# drive_monofasico_ir21844_vers_o_7_xx.net
KiCad netlist of a schematic drawn in EAGLE
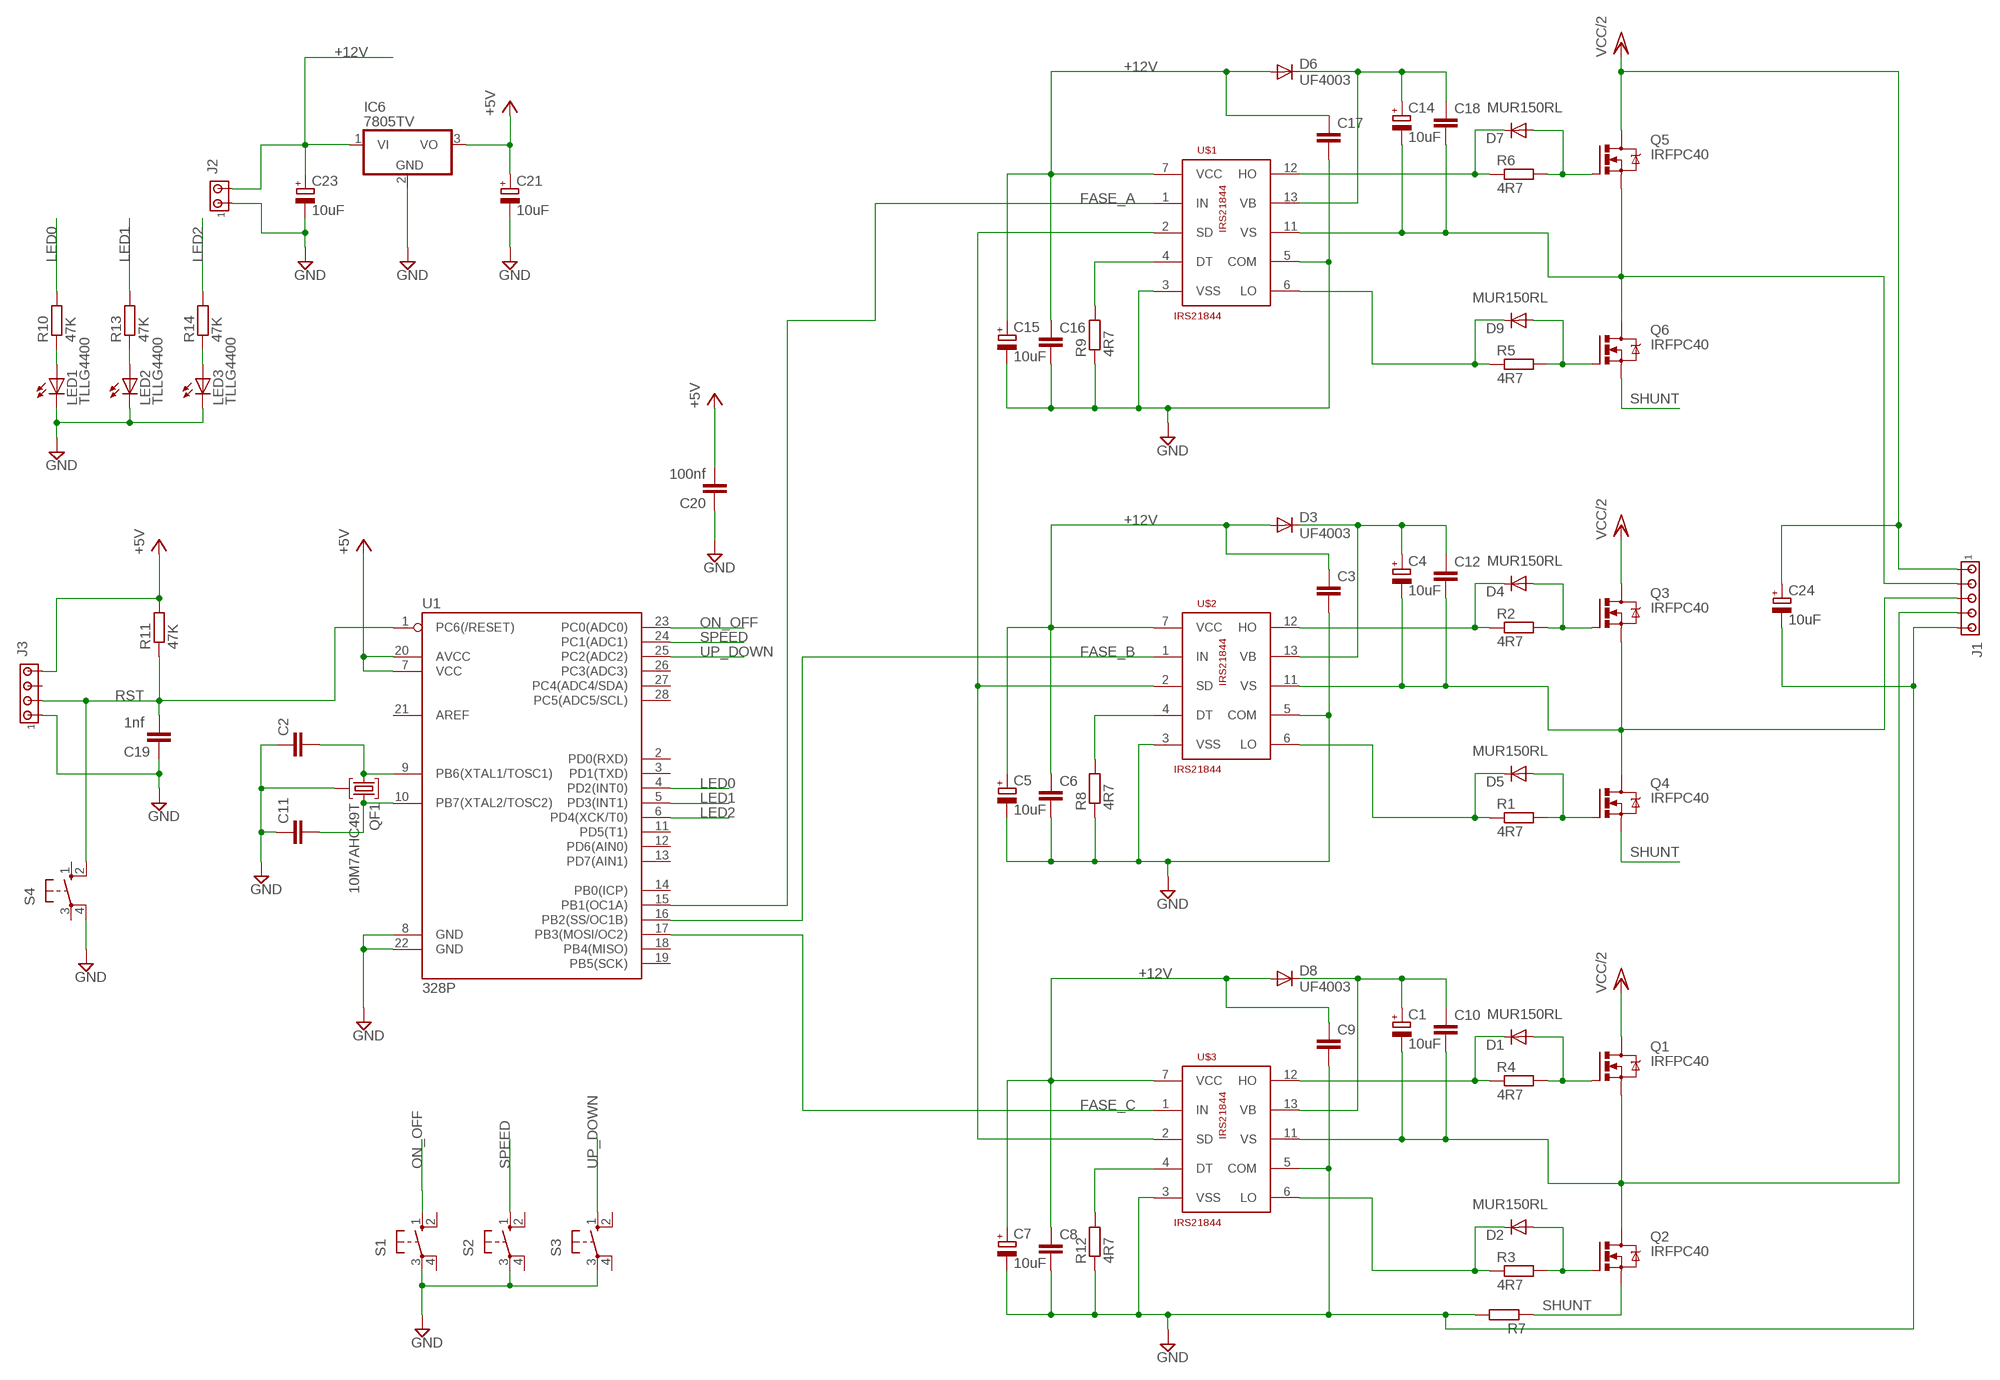
[diagram p0: schematic, sheet 1]

(export (version "E")
  (design (tool "Eeschema 10.0.6"))
  (components
    (comp (ref "C1")
      (value "10uF")
      (footprint "eagle-import:E5-6")
      (libsource (lib "eagle-import") (part "CPOL-EUE5-6"))
    )
    (comp (ref "C2")
      (value "C7.5/3")
      (footprint "eagle-import:C7.5B3")
      (libsource (lib "eagle-import") (part "C7.5/3"))
    )
    (comp (ref "C3")
      (value "C7.5/3")
      (footprint "eagle-import:C7.5B3")
      (libsource (lib "eagle-import") (part "C7.5/3"))
    )
    (comp (ref "C4")
      (value "10uF")
      (footprint "eagle-import:E5-6")
      (libsource (lib "eagle-import") (part "CPOL-EUE5-6"))
    )
    (comp (ref "C5")
      (value "10uF")
      (footprint "eagle-import:E5-6")
      (libsource (lib "eagle-import") (part "CPOL-EUE5-6"))
    )
    (comp (ref "C6")
      (value "C7.5/3")
      (footprint "eagle-import:C7.5B3")
      (libsource (lib "eagle-import") (part "C7.5/3"))
    )
    (comp (ref "C7")
      (value "10uF")
      (footprint "eagle-import:E5-6")
      (libsource (lib "eagle-import") (part "CPOL-EUE5-6"))
    )
    (comp (ref "C8")
      (value "C7.5/3")
      (footprint "eagle-import:C7.5B3")
      (libsource (lib "eagle-import") (part "C7.5/3"))
    )
    (comp (ref "C9")
      (value "C7.5/3")
      (footprint "eagle-import:C7.5B3")
      (libsource (lib "eagle-import") (part "C7.5/3"))
    )
    (comp (ref "C10")
      (value "C7.5/3")
      (footprint "eagle-import:C7.5B3")
      (libsource (lib "eagle-import") (part "C7.5/3"))
    )
    (comp (ref "C11")
      (value "C7.5/3")
      (footprint "eagle-import:C7.5B3")
      (libsource (lib "eagle-import") (part "C7.5/3"))
    )
    (comp (ref "C12")
      (value "C7.5/3")
      (footprint "eagle-import:C7.5B3")
      (libsource (lib "eagle-import") (part "C7.5/3"))
    )
    (comp (ref "C14")
      (value "10uF")
      (footprint "eagle-import:E5-6")
      (libsource (lib "eagle-import") (part "CPOL-EUE5-6"))
    )
    (comp (ref "C15")
      (value "10uF")
      (footprint "eagle-import:E5-6")
      (libsource (lib "eagle-import") (part "CPOL-EUE5-6"))
    )
    (comp (ref "C16")
      (value "C7.5/3")
      (footprint "eagle-import:C7.5B3")
      (libsource (lib "eagle-import") (part "C7.5/3"))
    )
    (comp (ref "C17")
      (value "C7.5/3")
      (footprint "eagle-import:C7.5B3")
      (libsource (lib "eagle-import") (part "C7.5/3"))
    )
    (comp (ref "C18")
      (value "C7.5/3")
      (footprint "eagle-import:C7.5B3")
      (libsource (lib "eagle-import") (part "C7.5/3"))
    )
    (comp (ref "C19")
      (value "1nf")
      (footprint "eagle-import:C050-025X075")
      (libsource (lib "eagle-import") (part "C-EU050-025X075"))
    )
    (comp (ref "C20")
      (value "100nf")
      (footprint "eagle-import:C050-025X075")
      (libsource (lib "eagle-import") (part "C-EU050-025X075"))
    )
    (comp (ref "C21")
      (value "10uF")
      (footprint "eagle-import:E5-6")
      (libsource (lib "eagle-import") (part "CPOL-EUE5-6"))
    )
    (comp (ref "C23")
      (value "10uF")
      (footprint "eagle-import:E5-6")
      (libsource (lib "eagle-import") (part "CPOL-EUE5-6"))
    )
    (comp (ref "C24")
      (value "10uF")
      (footprint "eagle-import:E5-6")
      (libsource (lib "eagle-import") (part "CPOL-EUE5-6"))
    )
    (comp (ref "D1")
      (value "MUR150RL")
      (footprint "eagle-import:DO41-10")
      (libsource (lib "eagle-import") (part "MUR150RL"))
    )
    (comp (ref "D2")
      (value "MUR150RL")
      (footprint "eagle-import:DO41-10")
      (libsource (lib "eagle-import") (part "MUR150RL"))
    )
    (comp (ref "D3")
      (value "UF4003")
      (footprint "eagle-import:DO41-10")
      (libsource (lib "eagle-import") (part "UF4003"))
    )
    (comp (ref "D4")
      (value "MUR150RL")
      (footprint "eagle-import:DO41-10")
      (libsource (lib "eagle-import") (part "MUR150RL"))
    )
    (comp (ref "D5")
      (value "MUR150RL")
      (footprint "eagle-import:DO41-10")
      (libsource (lib "eagle-import") (part "MUR150RL"))
    )
    (comp (ref "D6")
      (value "UF4003")
      (footprint "eagle-import:DO41-10")
      (libsource (lib "eagle-import") (part "UF4003"))
    )
    (comp (ref "D7")
      (value "MUR150RL")
      (footprint "eagle-import:DO41-10")
      (libsource (lib "eagle-import") (part "MUR150RL"))
    )
    (comp (ref "D8")
      (value "UF4003")
      (footprint "eagle-import:DO41-10")
      (libsource (lib "eagle-import") (part "UF4003"))
    )
    (comp (ref "D9")
      (value "MUR150RL")
      (footprint "eagle-import:DO41-10")
      (libsource (lib "eagle-import") (part "MUR150RL"))
    )
    (comp (ref "IC6")
      (value "7805TV")
      (footprint "eagle-import:TO220V")
      (libsource (lib "eagle-import") (part "78TV05"))
    )
    (comp (ref "J1")
      (value "MTA05-156")
      (footprint "eagle-import:1X5MTA")
      (libsource (lib "eagle-import") (part "MTA05-156"))
    )
    (comp (ref "J2")
      (value "MTA02-100")
      (footprint "eagle-import:10X02MTA")
      (libsource (lib "eagle-import") (part "MTA02-100"))
    )
    (comp (ref "J3")
      (value "MTA04-100")
      (footprint "eagle-import:10X04MTA")
      (libsource (lib "eagle-import") (part "MTA04-100"))
    )
    (comp (ref "LED1")
      (value "TLLG4400")
      (footprint "eagle-import:LED3MM")
      (fields (field (name "MF") "VISHAY SEMICONDUCTOR"))
      (libsource (lib "eagle-import") (part "TLLG4400"))
    )
    (comp (ref "LED2")
      (value "TLLG4400")
      (footprint "eagle-import:LED3MM")
      (fields (field (name "MF") "VISHAY SEMICONDUCTOR"))
      (libsource (lib "eagle-import") (part "TLLG4400"))
    )
    (comp (ref "LED3")
      (value "TLLG4400")
      (footprint "eagle-import:LED3MM")
      (fields (field (name "MF") "VISHAY SEMICONDUCTOR"))
      (libsource (lib "eagle-import") (part "TLLG4400"))
    )
    (comp (ref "Q1")
      (value "IRFPC40")
      (footprint "eagle-import:TO247BV")
      (libsource (lib "eagle-import") (part "IRFPC40"))
    )
    (comp (ref "Q2")
      (value "IRFPC40")
      (footprint "eagle-import:TO247BV")
      (libsource (lib "eagle-import") (part "IRFPC40"))
    )
    (comp (ref "Q3")
      (value "IRFPC40")
      (footprint "eagle-import:TO247BV")
      (libsource (lib "eagle-import") (part "IRFPC40"))
    )
    (comp (ref "Q4")
      (value "IRFPC40")
      (footprint "eagle-import:TO247BV")
      (libsource (lib "eagle-import") (part "IRFPC40"))
    )
    (comp (ref "Q5")
      (value "IRFPC40")
      (footprint "eagle-import:TO247BV")
      (libsource (lib "eagle-import") (part "IRFPC40"))
    )
    (comp (ref "Q6")
      (value "IRFPC40")
      (footprint "eagle-import:TO247BV")
      (libsource (lib "eagle-import") (part "IRFPC40"))
    )
    (comp (ref "QF1")
      (value "10M7AHC49T")
      (footprint "eagle-import:HC49U")
      (libsource (lib "eagle-import") (part "10MAHC49T7"))
    )
    (comp (ref "R1")
      (value "4R7")
      (footprint "eagle-import:0207_12")
      (libsource (lib "eagle-import") (part "R-EU_0207/12"))
    )
    (comp (ref "R2")
      (value "4R7")
      (footprint "eagle-import:0207_12")
      (libsource (lib "eagle-import") (part "R-EU_0207/12"))
    )
    (comp (ref "R3")
      (value "4R7")
      (footprint "eagle-import:0207_12")
      (libsource (lib "eagle-import") (part "R-EU_0207/12"))
    )
    (comp (ref "R4")
      (value "4R7")
      (footprint "eagle-import:0207_12")
      (libsource (lib "eagle-import") (part "R-EU_0207/12"))
    )
    (comp (ref "R5")
      (value "4R7")
      (footprint "eagle-import:0207_12")
      (libsource (lib "eagle-import") (part "R-EU_0207/12"))
    )
    (comp (ref "R6")
      (value "4R7")
      (footprint "eagle-import:0207_12")
      (libsource (lib "eagle-import") (part "R-EU_0207/12"))
    )
    (comp (ref "R7")
      (value "R-EU_0613/15")
      (footprint "eagle-import:P0613_15")
      (libsource (lib "eagle-import") (part "resistor_R-EU_0613/15"))
    )
    (comp (ref "R8")
      (value "4R7")
      (footprint "eagle-import:0207_12")
      (libsource (lib "eagle-import") (part "R-EU_0207/12"))
    )
    (comp (ref "R9")
      (value "4R7")
      (footprint "eagle-import:0207_12")
      (libsource (lib "eagle-import") (part "R-EU_0207/12"))
    )
    (comp (ref "R10")
      (value "47K")
      (footprint "eagle-import:0207_12")
      (libsource (lib "eagle-import") (part "resistor_R-EU_0207/12"))
    )
    (comp (ref "R11")
      (value "47K")
      (footprint "eagle-import:0207_12")
      (libsource (lib "eagle-import") (part "resistor_R-EU_0207/12"))
    )
    (comp (ref "R12")
      (value "4R7")
      (footprint "eagle-import:0207_12")
      (libsource (lib "eagle-import") (part "R-EU_0207/12"))
    )
    (comp (ref "R13")
      (value "47K")
      (footprint "eagle-import:0207_12")
      (libsource (lib "eagle-import") (part "resistor_R-EU_0207/12"))
    )
    (comp (ref "R14")
      (value "47K")
      (footprint "eagle-import:0207_12")
      (libsource (lib "eagle-import") (part "resistor_R-EU_0207/12"))
    )
    (comp (ref "S1")
      (value "10-XX")
      (footprint "eagle-import:B3F-10XX")
      (fields (field (name "MPN") "B3F-1000"))
      (libsource (lib "eagle-import") (part "10-XX"))
    )
    (comp (ref "S2")
      (value "10-XX")
      (footprint "eagle-import:B3F-10XX")
      (fields (field (name "MPN") "B3F-1000"))
      (libsource (lib "eagle-import") (part "10-XX"))
    )
    (comp (ref "S3")
      (value "10-XX")
      (footprint "eagle-import:B3F-10XX")
      (fields (field (name "MPN") "B3F-1000"))
      (libsource (lib "eagle-import") (part "10-XX"))
    )
    (comp (ref "S4")
      (value "10-XX")
      (footprint "eagle-import:B3F-10XX")
      (fields (field (name "MPN") "B3F-1000"))
      (libsource (lib "eagle-import") (part "10-XX"))
    )
    (comp (ref "U$1")
      (value "IRS21844")
      (footprint "eagle-import:IRS21844")
      (libsource (lib "eagle-import") (part "IRS21844"))
    )
    (comp (ref "U$2")
      (value "IRS21844")
      (footprint "eagle-import:IRS21844")
      (libsource (lib "eagle-import") (part "IRS21844"))
    )
    (comp (ref "U$3")
      (value "IRS21844")
      (footprint "eagle-import:IRS21844")
      (libsource (lib "eagle-import") (part "IRS21844"))
    )
    (comp (ref "U1")
      (value "328P")
      (footprint "eagle-import:DIP28")
      (libsource (lib "eagle-import") (part "ATMEGA328P_PDIP"))
    )
  )
  (nets
    (net (code "1") (name "+5V") (class "Default")
      (node (ref "C20") (pin "2") (pinfunction "2_2") (pintype "passive"))
      (node (ref "C21") (pin "+") (pinfunction "+_+") (pintype "passive"))
      (node (ref "IC6") (pin "3") (pinfunction "VO_3") (pintype "passive"))
      (node (ref "J3") (pin "4") (pinfunction "4_4") (pintype "passive"))
      (node (ref "R11") (pin "2") (pinfunction "2_2") (pintype "passive"))
      (node (ref "U1") (pin "20") (pinfunction "AVCC_20") (pintype "bidirectional"))
      (node (ref "U1") (pin "7") (pinfunction "VCC_7") (pintype "bidirectional"))
    )
    (net (code "2") (name "/+12V") (class "Default")
      (node (ref "C15") (pin "+") (pinfunction "+_+") (pintype "passive"))
      (node (ref "C16") (pin "1") (pinfunction "1_1") (pintype "passive"))
      (node (ref "C17") (pin "1") (pinfunction "1_1") (pintype "passive"))
      (node (ref "C23") (pin "+") (pinfunction "+_+") (pintype "passive"))
      (node (ref "C3") (pin "1") (pinfunction "1_1") (pintype "passive"))
      (node (ref "C5") (pin "+") (pinfunction "+_+") (pintype "passive"))
      (node (ref "C6") (pin "1") (pinfunction "1_1") (pintype "passive"))
      (node (ref "C7") (pin "+") (pinfunction "+_+") (pintype "passive"))
      (node (ref "C8") (pin "1") (pinfunction "1_1") (pintype "passive"))
      (node (ref "C9") (pin "1") (pinfunction "1_1") (pintype "passive"))
      (node (ref "D3") (pin "A") (pinfunction "A_A") (pintype "passive"))
      (node (ref "D6") (pin "A") (pinfunction "A_A") (pintype "passive"))
      (node (ref "D8") (pin "A") (pinfunction "A_A") (pintype "passive"))
      (node (ref "IC6") (pin "1") (pinfunction "VI_1") (pintype "input"))
      (node (ref "J2") (pin "2") (pinfunction "2_2") (pintype "passive"))
      (node (ref "U$1") (pin "7") (pinfunction "VCC_7") (pintype "bidirectional"))
      (node (ref "U$2") (pin "7") (pinfunction "VCC_7") (pintype "bidirectional"))
      (node (ref "U$3") (pin "7") (pinfunction "VCC_7") (pintype "bidirectional"))
    )
    (net (code "3") (name "/FASE_A") (class "Default")
      (node (ref "U$1") (pin "1") (pinfunction "IN_1") (pintype "bidirectional"))
      (node (ref "U1") (pin "15") (pinfunction "PB1(OC1A)_15") (pintype "bidirectional"))
    )
    (net (code "4") (name "/FASE_B") (class "Default")
      (node (ref "U$2") (pin "1") (pinfunction "IN_1") (pintype "bidirectional"))
      (node (ref "U1") (pin "16") (pinfunction "PB2(SS/OC1B)_16") (pintype "bidirectional"))
    )
    (net (code "5") (name "/FASE_C") (class "Default")
      (node (ref "U$3") (pin "1") (pinfunction "IN_1") (pintype "bidirectional"))
      (node (ref "U1") (pin "17") (pinfunction "PB3(MOSI/OC2)_17") (pintype "bidirectional"))
    )
    (net (code "6") (name "/LED0") (class "Default")
      (node (ref "R10") (pin "2") (pinfunction "2_2") (pintype "passive"))
      (node (ref "U1") (pin "4") (pinfunction "PD2(INT0)_4") (pintype "bidirectional"))
    )
    (net (code "7") (name "/LED1") (class "Default")
      (node (ref "R13") (pin "2") (pinfunction "2_2") (pintype "passive"))
      (node (ref "U1") (pin "5") (pinfunction "PD3(INT1)_5") (pintype "bidirectional"))
    )
    (net (code "8") (name "/LED2") (class "Default")
      (node (ref "R14") (pin "2") (pinfunction "2_2") (pintype "passive"))
      (node (ref "U1") (pin "6") (pinfunction "PD4(XCK/T0)_6") (pintype "bidirectional"))
    )
    (net (code "9") (name "/ON_OFF") (class "Default")
      (node (ref "S1") (pin "1") (pinfunction "S_1") (pintype "passive"))
      (node (ref "U1") (pin "23") (pinfunction "PC0(ADC0)_23") (pintype "bidirectional"))
    )
    (net (code "10") (name "/RST") (class "Default")
      (node (ref "C19") (pin "1") (pinfunction "1_1") (pintype "passive"))
      (node (ref "J3") (pin "2") (pinfunction "2_2") (pintype "passive"))
      (node (ref "R11") (pin "1") (pinfunction "1_1") (pintype "passive"))
      (node (ref "S4") (pin "2") (pinfunction "S1_2") (pintype "passive"))
      (node (ref "U1") (pin "1") (pinfunction "PC6(/RESET)_1") (pintype "bidirectional"))
    )
    (net (code "11") (name "/SHUNT") (class "Default")
      (node (ref "Q2") (pin "S") (pinfunction "S_S") (pintype "passive"))
      (node (ref "Q4") (pin "S") (pinfunction "S_S") (pintype "passive"))
      (node (ref "Q6") (pin "S") (pinfunction "S_S") (pintype "passive"))
      (node (ref "R7") (pin "1") (pinfunction "1_1") (pintype "passive"))
    )
    (net (code "12") (name "/SPEED") (class "Default")
      (node (ref "S2") (pin "1") (pinfunction "S_1") (pintype "passive"))
      (node (ref "U1") (pin "24") (pinfunction "PC1(ADC1)_24") (pintype "bidirectional"))
    )
    (net (code "13") (name "/UP_DOWN") (class "Default")
      (node (ref "S3") (pin "1") (pinfunction "S_1") (pintype "passive"))
      (node (ref "U1") (pin "25") (pinfunction "PC2(ADC2)_25") (pintype "bidirectional"))
    )
    (net (code "14") (name "GND") (class "Default")
      (node (ref "C11") (pin "1") (pinfunction "1_1") (pintype "passive"))
      (node (ref "C15") (pin "-") (pinfunction "-_-") (pintype "passive"))
      (node (ref "C16") (pin "2") (pinfunction "2_2") (pintype "passive"))
      (node (ref "C17") (pin "2") (pinfunction "2_2") (pintype "passive"))
      (node (ref "C19") (pin "2") (pinfunction "2_2") (pintype "passive"))
      (node (ref "C2") (pin "1") (pinfunction "1_1") (pintype "passive"))
      (node (ref "C20") (pin "1") (pinfunction "1_1") (pintype "passive"))
      (node (ref "C21") (pin "-") (pinfunction "-_-") (pintype "passive"))
      (node (ref "C23") (pin "-") (pinfunction "-_-") (pintype "passive"))
      (node (ref "C24") (pin "-") (pinfunction "-_-") (pintype "passive"))
      (node (ref "C3") (pin "2") (pinfunction "2_2") (pintype "passive"))
      (node (ref "C5") (pin "-") (pinfunction "-_-") (pintype "passive"))
      (node (ref "C6") (pin "2") (pinfunction "2_2") (pintype "passive"))
      (node (ref "C7") (pin "-") (pinfunction "-_-") (pintype "passive"))
      (node (ref "C8") (pin "2") (pinfunction "2_2") (pintype "passive"))
      (node (ref "C9") (pin "2") (pinfunction "2_2") (pintype "passive"))
      (node (ref "IC6") (pin "2") (pinfunction "GND_2") (pintype "passive"))
      (node (ref "J1") (pin "5") (pinfunction "5_5") (pintype "passive"))
      (node (ref "J2") (pin "1") (pinfunction "1_1") (pintype "passive"))
      (node (ref "J3") (pin "1") (pinfunction "1_1") (pintype "passive"))
      (node (ref "LED1") (pin "K") (pinfunction "C_K") (pintype "passive"))
      (node (ref "LED2") (pin "K") (pinfunction "C_K") (pintype "passive"))
      (node (ref "LED3") (pin "K") (pinfunction "C_K") (pintype "passive"))
      (node (ref "QF1") (pin "2") (pinfunction "2_2") (pintype "passive"))
      (node (ref "R12") (pin "1") (pinfunction "1_1") (pintype "passive"))
      (node (ref "R7") (pin "2") (pinfunction "2_2") (pintype "passive"))
      (node (ref "R8") (pin "1") (pinfunction "1_1") (pintype "passive"))
      (node (ref "R9") (pin "1") (pinfunction "1_1") (pintype "passive"))
      (node (ref "S1") (pin "3") (pinfunction "P_3") (pintype "passive"))
      (node (ref "S2") (pin "3") (pinfunction "P_3") (pintype "passive"))
      (node (ref "S3") (pin "3") (pinfunction "P_3") (pintype "passive"))
      (node (ref "S4") (pin "4") (pinfunction "P1_4") (pintype "passive"))
      (node (ref "U$1") (pin "3") (pinfunction "VSS_3") (pintype "bidirectional"))
      (node (ref "U$1") (pin "5") (pinfunction "COM_5") (pintype "bidirectional"))
      (node (ref "U$2") (pin "3") (pinfunction "VSS_3") (pintype "bidirectional"))
      (node (ref "U$2") (pin "5") (pinfunction "COM_5") (pintype "bidirectional"))
      (node (ref "U$3") (pin "3") (pinfunction "VSS_3") (pintype "bidirectional"))
      (node (ref "U$3") (pin "5") (pinfunction "COM_5") (pintype "bidirectional"))
      (node (ref "U1") (pin "22") (pinfunction "GND_22") (pintype "bidirectional"))
      (node (ref "U1") (pin "8") (pinfunction "GND_8") (pintype "bidirectional"))
    )
    (net (code "15") (name "Net-(D1-PadA)") (class "Default")
      (node (ref "D1") (pin "A") (pinfunction "A_A") (pintype "passive"))
      (node (ref "Q1") (pin "G") (pinfunction "G_G") (pintype "passive"))
      (node (ref "R4") (pin "2") (pinfunction "2_2") (pintype "passive"))
    )
    (net (code "16") (name "Net-(D2-PadA)") (class "Default")
      (node (ref "D2") (pin "A") (pinfunction "A_A") (pintype "passive"))
      (node (ref "Q2") (pin "G") (pinfunction "G_G") (pintype "passive"))
      (node (ref "R3") (pin "2") (pinfunction "2_2") (pintype "passive"))
    )
    (net (code "17") (name "Net-(D4-PadA)") (class "Default")
      (node (ref "D4") (pin "A") (pinfunction "A_A") (pintype "passive"))
      (node (ref "Q3") (pin "G") (pinfunction "G_G") (pintype "passive"))
      (node (ref "R2") (pin "2") (pinfunction "2_2") (pintype "passive"))
    )
    (net (code "18") (name "Net-(D5-PadA)") (class "Default")
      (node (ref "D5") (pin "A") (pinfunction "A_A") (pintype "passive"))
      (node (ref "Q4") (pin "G") (pinfunction "G_G") (pintype "passive"))
      (node (ref "R1") (pin "2") (pinfunction "2_2") (pintype "passive"))
    )
    (net (code "19") (name "Net-(D7-PadA)") (class "Default")
      (node (ref "D7") (pin "A") (pinfunction "A_A") (pintype "passive"))
      (node (ref "Q5") (pin "G") (pinfunction "G_G") (pintype "passive"))
      (node (ref "R6") (pin "2") (pinfunction "2_2") (pintype "passive"))
    )
    (net (code "20") (name "Net-(D9-PadA)") (class "Default")
      (node (ref "D9") (pin "A") (pinfunction "A_A") (pintype "passive"))
      (node (ref "Q6") (pin "G") (pinfunction "G_G") (pintype "passive"))
      (node (ref "R5") (pin "2") (pinfunction "2_2") (pintype "passive"))
    )
    (net (code "21") (name "Net-(LED1-PadA)") (class "Default")
      (node (ref "LED1") (pin "A") (pinfunction "A_A") (pintype "passive"))
      (node (ref "R10") (pin "1") (pinfunction "1_1") (pintype "passive"))
    )
    (net (code "22") (name "Net-(LED2-PadA)") (class "Default")
      (node (ref "LED2") (pin "A") (pinfunction "A_A") (pintype "passive"))
      (node (ref "R13") (pin "1") (pinfunction "1_1") (pintype "passive"))
    )
    (net (code "23") (name "Net-(LED3-PadA)") (class "Default")
      (node (ref "LED3") (pin "A") (pinfunction "A_A") (pintype "passive"))
      (node (ref "R14") (pin "1") (pinfunction "1_1") (pintype "passive"))
    )
    (net (code "24") (name "Net-(U$1-DT)") (class "Default")
      (node (ref "R9") (pin "2") (pinfunction "2_2") (pintype "passive"))
      (node (ref "U$1") (pin "4") (pinfunction "DT_4") (pintype "bidirectional"))
    )
    (net (code "25") (name "Net-(U$1-HO)") (class "Default")
      (node (ref "D7") (pin "C") (pinfunction "C_C") (pintype "passive"))
      (node (ref "R6") (pin "1") (pinfunction "1_1") (pintype "passive"))
      (node (ref "U$1") (pin "12") (pinfunction "HO_12") (pintype "bidirectional"))
    )
    (net (code "26") (name "Net-(U$1-LO)") (class "Default")
      (node (ref "D9") (pin "C") (pinfunction "C_C") (pintype "passive"))
      (node (ref "R5") (pin "1") (pinfunction "1_1") (pintype "passive"))
      (node (ref "U$1") (pin "6") (pinfunction "LO_6") (pintype "bidirectional"))
    )
    (net (code "27") (name "Net-(U$1-SD)") (class "Default")
      (node (ref "U$1") (pin "2") (pinfunction "SD_2") (pintype "bidirectional"))
      (node (ref "U$2") (pin "2") (pinfunction "SD_2") (pintype "bidirectional"))
      (node (ref "U$3") (pin "2") (pinfunction "SD_2") (pintype "bidirectional"))
    )
    (net (code "28") (name "Net-(U$1-VB)") (class "Default")
      (node (ref "C14") (pin "+") (pinfunction "+_+") (pintype "passive"))
      (node (ref "C18") (pin "1") (pinfunction "1_1") (pintype "passive"))
      (node (ref "D6") (pin "C") (pinfunction "C_C") (pintype "passive"))
      (node (ref "U$1") (pin "13") (pinfunction "VB_13") (pintype "bidirectional"))
    )
    (net (code "29") (name "Net-(U$1-VS)") (class "Default")
      (node (ref "C14") (pin "-") (pinfunction "-_-") (pintype "passive"))
      (node (ref "C18") (pin "2") (pinfunction "2_2") (pintype "passive"))
      (node (ref "J1") (pin "2") (pinfunction "2_2") (pintype "passive"))
      (node (ref "Q5") (pin "S") (pinfunction "S_S") (pintype "passive"))
      (node (ref "Q6") (pin "D") (pinfunction "D_D") (pintype "passive"))
      (node (ref "U$1") (pin "11") (pinfunction "VS_11") (pintype "bidirectional"))
    )
    (net (code "30") (name "Net-(U$2-DT)") (class "Default")
      (node (ref "R8") (pin "2") (pinfunction "2_2") (pintype "passive"))
      (node (ref "U$2") (pin "4") (pinfunction "DT_4") (pintype "bidirectional"))
    )
    (net (code "31") (name "Net-(U$2-HO)") (class "Default")
      (node (ref "D4") (pin "C") (pinfunction "C_C") (pintype "passive"))
      (node (ref "R2") (pin "1") (pinfunction "1_1") (pintype "passive"))
      (node (ref "U$2") (pin "12") (pinfunction "HO_12") (pintype "bidirectional"))
    )
    (net (code "32") (name "Net-(U$2-LO)") (class "Default")
      (node (ref "D5") (pin "C") (pinfunction "C_C") (pintype "passive"))
      (node (ref "R1") (pin "1") (pinfunction "1_1") (pintype "passive"))
      (node (ref "U$2") (pin "6") (pinfunction "LO_6") (pintype "bidirectional"))
    )
    (net (code "33") (name "Net-(U$2-VB)") (class "Default")
      (node (ref "C12") (pin "1") (pinfunction "1_1") (pintype "passive"))
      (node (ref "C4") (pin "+") (pinfunction "+_+") (pintype "passive"))
      (node (ref "D3") (pin "C") (pinfunction "C_C") (pintype "passive"))
      (node (ref "U$2") (pin "13") (pinfunction "VB_13") (pintype "bidirectional"))
    )
    (net (code "34") (name "Net-(U$2-VS)") (class "Default")
      (node (ref "C12") (pin "2") (pinfunction "2_2") (pintype "passive"))
      (node (ref "C4") (pin "-") (pinfunction "-_-") (pintype "passive"))
      (node (ref "J1") (pin "3") (pinfunction "3_3") (pintype "passive"))
      (node (ref "Q3") (pin "S") (pinfunction "S_S") (pintype "passive"))
      (node (ref "Q4") (pin "D") (pinfunction "D_D") (pintype "passive"))
      (node (ref "U$2") (pin "11") (pinfunction "VS_11") (pintype "bidirectional"))
    )
    (net (code "35") (name "Net-(U$3-DT)") (class "Default")
      (node (ref "R12") (pin "2") (pinfunction "2_2") (pintype "passive"))
      (node (ref "U$3") (pin "4") (pinfunction "DT_4") (pintype "bidirectional"))
    )
    (net (code "36") (name "Net-(U$3-HO)") (class "Default")
      (node (ref "D1") (pin "C") (pinfunction "C_C") (pintype "passive"))
      (node (ref "R4") (pin "1") (pinfunction "1_1") (pintype "passive"))
      (node (ref "U$3") (pin "12") (pinfunction "HO_12") (pintype "bidirectional"))
    )
    (net (code "37") (name "Net-(U$3-LO)") (class "Default")
      (node (ref "D2") (pin "C") (pinfunction "C_C") (pintype "passive"))
      (node (ref "R3") (pin "1") (pinfunction "1_1") (pintype "passive"))
      (node (ref "U$3") (pin "6") (pinfunction "LO_6") (pintype "bidirectional"))
    )
    (net (code "38") (name "Net-(U$3-VB)") (class "Default")
      (node (ref "C1") (pin "+") (pinfunction "+_+") (pintype "passive"))
      (node (ref "C10") (pin "1") (pinfunction "1_1") (pintype "passive"))
      (node (ref "D8") (pin "C") (pinfunction "C_C") (pintype "passive"))
      (node (ref "U$3") (pin "13") (pinfunction "VB_13") (pintype "bidirectional"))
    )
    (net (code "39") (name "Net-(U$3-VS)") (class "Default")
      (node (ref "C1") (pin "-") (pinfunction "-_-") (pintype "passive"))
      (node (ref "C10") (pin "2") (pinfunction "2_2") (pintype "passive"))
      (node (ref "J1") (pin "4") (pinfunction "4_4") (pintype "passive"))
      (node (ref "Q1") (pin "S") (pinfunction "S_S") (pintype "passive"))
      (node (ref "Q2") (pin "D") (pinfunction "D_D") (pintype "passive"))
      (node (ref "U$3") (pin "11") (pinfunction "VS_11") (pintype "bidirectional"))
    )
    (net (code "40") (name "Net-(U1-PB6(XTAL1{slash}TOSC1))") (class "Default")
      (node (ref "C2") (pin "2") (pinfunction "2_2") (pintype "passive"))
      (node (ref "QF1") (pin "1") (pinfunction "1_1") (pintype "passive"))
      (node (ref "U1") (pin "9") (pinfunction "PB6(XTAL1/TOSC1)_9") (pintype "bidirectional"))
    )
    (net (code "41") (name "Net-(U1-PB7(XTAL2{slash}TOSC2))") (class "Default")
      (node (ref "C11") (pin "2") (pinfunction "2_2") (pintype "passive"))
      (node (ref "QF1") (pin "3") (pinfunction "3_3") (pintype "passive"))
      (node (ref "U1") (pin "10") (pinfunction "PB7(XTAL2/TOSC2)_10") (pintype "bidirectional"))
    )
    (net (code "42") (name "VCC{slash}2") (class "Default")
      (node (ref "C24") (pin "+") (pinfunction "+_+") (pintype "passive"))
      (node (ref "J1") (pin "1") (pinfunction "1_1") (pintype "passive"))
      (node (ref "Q1") (pin "D") (pinfunction "D_D") (pintype "passive"))
      (node (ref "Q3") (pin "D") (pinfunction "D_D") (pintype "passive"))
      (node (ref "Q5") (pin "D") (pinfunction "D_D") (pintype "passive"))
    )
    (net (code "43") (name "unconnected-(J3-Pad3)") (class "Default")
      (node (ref "J3") (pin "3") (pinfunction "3_3") (pintype "passive"))
    )
    (net (code "44") (name "unconnected-(S1-P1-Pad4)") (class "Default")
      (node (ref "S1") (pin "4") (pinfunction "P1_4") (pintype "passive"))
    )
    (net (code "45") (name "unconnected-(S1-S1-Pad2)") (class "Default")
      (node (ref "S1") (pin "2") (pinfunction "S1_2") (pintype "passive"))
    )
    (net (code "46") (name "unconnected-(S2-P1-Pad4)") (class "Default")
      (node (ref "S2") (pin "4") (pinfunction "P1_4") (pintype "passive"))
    )
    (net (code "47") (name "unconnected-(S2-S1-Pad2)") (class "Default")
      (node (ref "S2") (pin "2") (pinfunction "S1_2") (pintype "passive"))
    )
    (net (code "48") (name "unconnected-(S3-P1-Pad4)") (class "Default")
      (node (ref "S3") (pin "4") (pinfunction "P1_4") (pintype "passive"))
    )
    (net (code "49") (name "unconnected-(S3-S1-Pad2)") (class "Default")
      (node (ref "S3") (pin "2") (pinfunction "S1_2") (pintype "passive"))
    )
    (net (code "50") (name "unconnected-(S4-P-Pad3)") (class "Default")
      (node (ref "S4") (pin "3") (pinfunction "P_3") (pintype "passive"))
    )
    (net (code "51") (name "unconnected-(S4-S-Pad1)") (class "Default")
      (node (ref "S4") (pin "1") (pinfunction "S_1") (pintype "passive"))
    )
    (net (code "52") (name "unconnected-(U1-AREF-Pad21)") (class "Default")
      (node (ref "U1") (pin "21") (pinfunction "AREF_21") (pintype "bidirectional"))
    )
    (net (code "53") (name "unconnected-(U1-PB0(ICP)-Pad14)") (class "Default")
      (node (ref "U1") (pin "14") (pinfunction "PB0(ICP)_14") (pintype "bidirectional"))
    )
    (net (code "54") (name "unconnected-(U1-PB4(MISO)-Pad18)") (class "Default")
      (node (ref "U1") (pin "18") (pinfunction "PB4(MISO)_18") (pintype "bidirectional"))
    )
    (net (code "55") (name "unconnected-(U1-PB5(SCK)-Pad19)") (class "Default")
      (node (ref "U1") (pin "19") (pinfunction "PB5(SCK)_19") (pintype "bidirectional"))
    )
    (net (code "56") (name "unconnected-(U1-PC3(ADC3)-Pad26)") (class "Default")
      (node (ref "U1") (pin "26") (pinfunction "PC3(ADC3)_26") (pintype "bidirectional"))
    )
    (net (code "57") (name "unconnected-(U1-PC4(ADC4{slash}SDA)-Pad27)") (class "Default")
      (node (ref "U1") (pin "27") (pinfunction "PC4(ADC4/SDA)_27") (pintype "bidirectional"))
    )
    (net (code "58") (name "unconnected-(U1-PC5(ADC5{slash}SCL)-Pad28)") (class "Default")
      (node (ref "U1") (pin "28") (pinfunction "PC5(ADC5/SCL)_28") (pintype "bidirectional"))
    )
    (net (code "59") (name "unconnected-(U1-PD0(RXD)-Pad2)") (class "Default")
      (node (ref "U1") (pin "2") (pinfunction "PD0(RXD)_2") (pintype "bidirectional"))
    )
    (net (code "60") (name "unconnected-(U1-PD1(TXD)-Pad3)") (class "Default")
      (node (ref "U1") (pin "3") (pinfunction "PD1(TXD)_3") (pintype "bidirectional"))
    )
    (net (code "61") (name "unconnected-(U1-PD5(T1)-Pad11)") (class "Default")
      (node (ref "U1") (pin "11") (pinfunction "PD5(T1)_11") (pintype "bidirectional"))
    )
    (net (code "62") (name "unconnected-(U1-PD6(AIN0)-Pad12)") (class "Default")
      (node (ref "U1") (pin "12") (pinfunction "PD6(AIN0)_12") (pintype "bidirectional"))
    )
    (net (code "63") (name "unconnected-(U1-PD7(AIN1)-Pad13)") (class "Default")
      (node (ref "U1") (pin "13") (pinfunction "PD7(AIN1)_13") (pintype "bidirectional"))
    )
  )
)
